# C_3.net
KiCad netlist of a schematic drawn in EasyEDA Pro
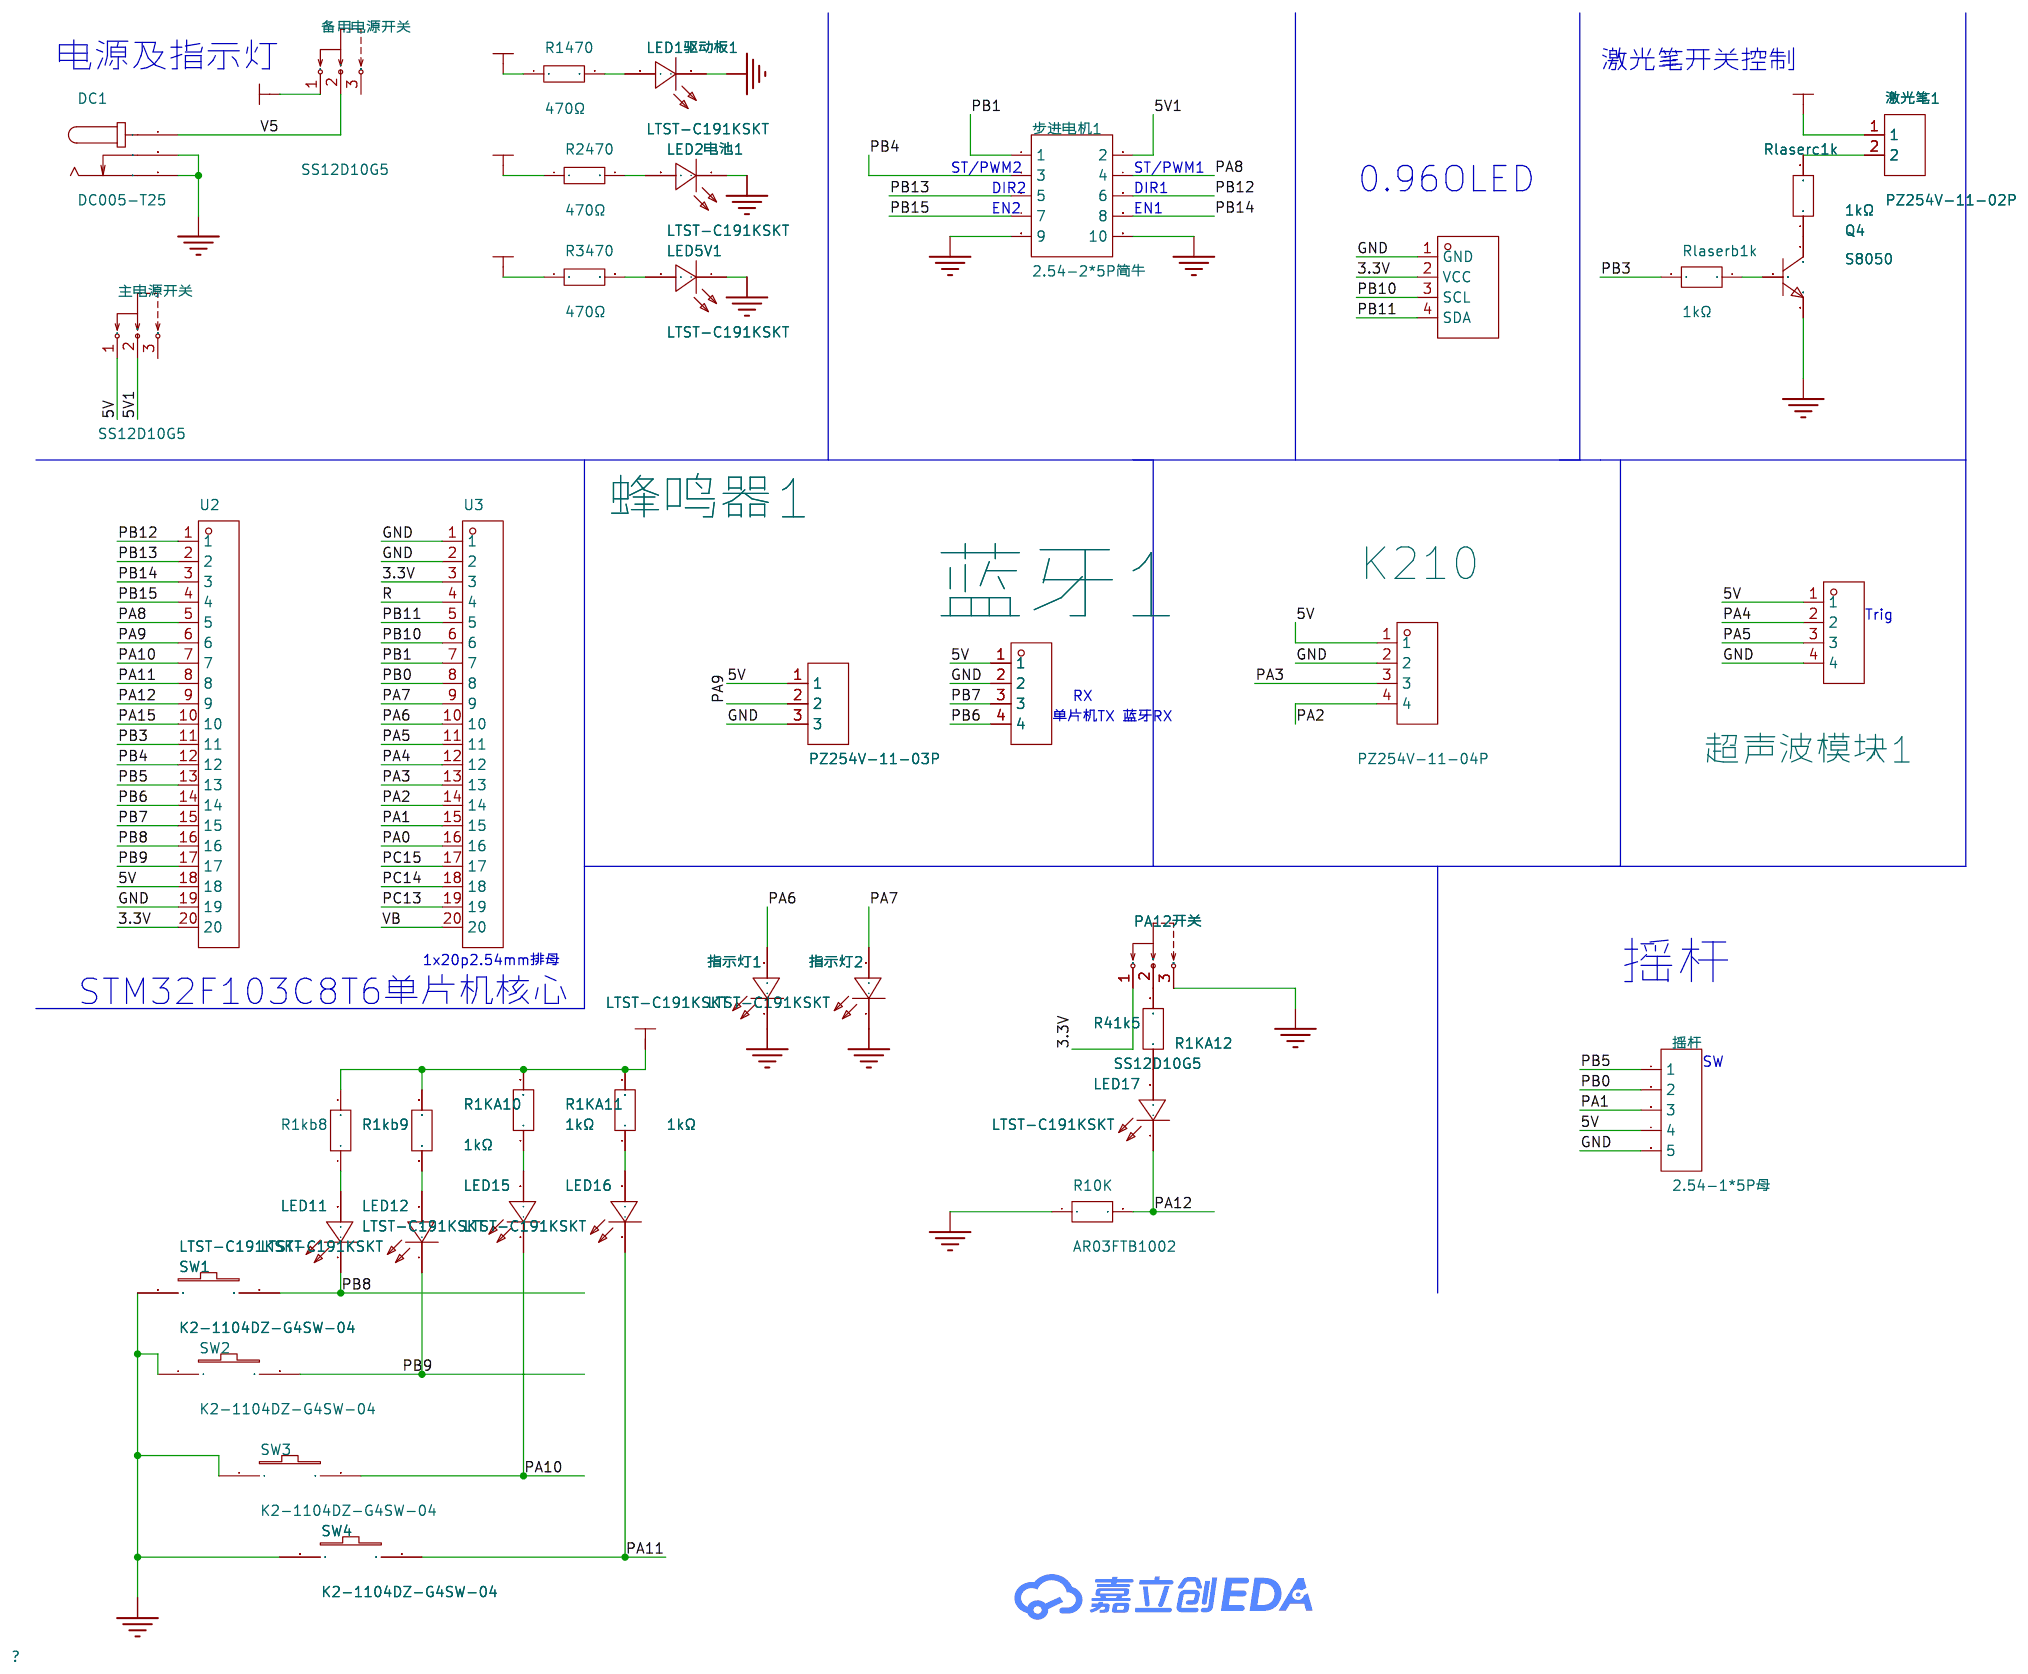
[diagram p0: schematic sheet]

(export (version "E")
  (design (tool "Eeschema 10.0.6"))
  (components
    (comp (ref "DC1")
      (value "DC005-T25")
      (footprint "easyedapro:DC-IN-TH_DC-005-20A-1")
      (description "触点内径:2.5mm;触点外径:6.3mm;额定电流:-;额定电压:-;")
      (fields (field (name "Manufacturer") "SOFNG(硕方)"))
      (libsource (lib "easyedapro") (part "DC005-2.5MM"))
    )
    (comp (ref "K210")
      (value "PZ254V-11-04P")
      (footprint "easyedapro:HDR-TH_4P-P2.54-V-M")
      (fields (field (name "Manufacturer") "XFCN(兴飞)"))
      (libsource (lib "easyedapro") (part "PZ254V-11-04P_C2691448"))
    )
    (comp (ref "LED1驱动板1")
      (value "LTST-C191KSKT")
      (footprint "easyedapro:LED0603-RD-YELLOW")
      (fields (field (name "Manufacturer") "LITEON(光宝)"))
      (libsource (lib "easyedapro") (part "LTST-C191KSKT"))
    )
    (comp (ref "LED2电池1")
      (value "LTST-C191KSKT")
      (footprint "easyedapro:LED0603-RD-YELLOW")
      (fields (field (name "Manufacturer") "LITEON(光宝)"))
      (libsource (lib "easyedapro") (part "LTST-C191KSKT"))
    )
    (comp (ref "LED5V1")
      (value "LTST-C191KSKT")
      (footprint "easyedapro:LED0603-RD-YELLOW")
      (fields (field (name "Manufacturer") "LITEON(光宝)"))
      (libsource (lib "easyedapro") (part "LTST-C191KSKT"))
    )
    (comp (ref "LED11")
      (value "LTST-C191KSKT")
      (footprint "easyedapro:LED0603-RD-YELLOW")
      (fields (field (name "Manufacturer") "LITEON(光宝)"))
      (libsource (lib "easyedapro") (part "LTST-C191KSKT"))
    )
    (comp (ref "LED12")
      (value "LTST-C191KSKT")
      (footprint "easyedapro:LED0603-RD-YELLOW")
      (fields (field (name "Manufacturer") "LITEON(光宝)"))
      (libsource (lib "easyedapro") (part "LTST-C191KSKT"))
    )
    (comp (ref "LED15")
      (value "LTST-C191KSKT")
      (footprint "easyedapro:LED0603-RD-YELLOW")
      (fields (field (name "Manufacturer") "LITEON(光宝)"))
      (libsource (lib "easyedapro") (part "LTST-C191KSKT"))
    )
    (comp (ref "LED16")
      (value "LTST-C191KSKT")
      (footprint "easyedapro:LED0603-RD-YELLOW")
      (fields (field (name "Manufacturer") "LITEON(光宝)"))
      (libsource (lib "easyedapro") (part "LTST-C191KSKT"))
    )
    (comp (ref "LED17")
      (value "LTST-C191KSKT")
      (footprint "easyedapro:LED0603-RD-YELLOW")
      (fields (field (name "Manufacturer") "LITEON(光宝)"))
      (libsource (lib "easyedapro") (part "LTST-C191KSKT"))
    )
    (comp (ref "OLED1")
      (value "HS96L03W2C03")
      (footprint "easyedapro:OLED-TH_L27.8-W27.2-P2.54_C9900033791")
      (description "主控芯片:SSD1315;接口类型:I2C;尺寸(inch):0.96;像素分辨率:128x64;")
      (fields (field (name "Manufacturer") "HS(汉昇)"))
      (libsource (lib "easyedapro") (part "HS96L03W2C03"))
    )
    (comp (ref "PA12开关")
      (value "SS12D10G5")
      (footprint "easyedapro:SW-TH_SHOU-HAN_SS12D10G4")
      (description "电路结构:单刀双掷;安装方式:直插;额定电流(DC):2A;额定电压(DC):125V;机械寿命:3千次;")
      (fields (field (name "Manufacturer") "SHOU HAN(首韩)"))
      (libsource (lib "easyedapro") (part "SS12D10G5"))
    )
    (comp (ref "Q4")
      (value "S8050")
      (footprint "easyedapro:SOT-23-3_L2.9-W1.6-P1.90-LS2.8-BR")
      (description "晶体管类型:NPN;集电极电流(Ic):500mA;集射极击穿电压(Vceo):25V;功率(Pd):300mW;")
      (fields (field (name "Manufacturer") "Hottech(合科泰)"))
      (libsource (lib "easyedapro") (part "S8050_C181158"))
    )
    (comp (ref "R1KA10")
      (value "1kΩ")
      (footprint "easyedapro:R0603")
      (description "电阻类型:厚膜电阻;阻值:1kΩ;精度:±1%;功率:100mW;最大工作电压:75V;")
      (fields (field (name "Manufacturer Part") "FCR0603F1K") (field (name "Manufacturer") "VO(翔胜)"))
      (libsource (lib "easyedapro") (part "FCR0603F1K"))
    )
    (comp (ref "R1KA11")
      (value "1kΩ")
      (footprint "easyedapro:R0603")
      (description "电阻类型:厚膜电阻;阻值:1kΩ;精度:±1%;功率:100mW;最大工作电压:75V;")
      (fields (field (name "Manufacturer Part") "FCR0603F1K") (field (name "Manufacturer") "VO(翔胜)"))
      (libsource (lib "easyedapro") (part "FCR0603F1K"))
    )
    (comp (ref "R1kb8")
      (value "1kΩ")
      (footprint "easyedapro:R0603")
      (description "电阻类型:厚膜电阻;阻值:1kΩ;精度:±1%;功率:100mW;最大工作电压:75V;")
      (fields (field (name "Manufacturer Part") "FCR0603F1K") (field (name "Manufacturer") "VO(翔胜)"))
      (libsource (lib "easyedapro") (part "FCR0603F1K"))
    )
    (comp (ref "R1kb9")
      (value "1kΩ")
      (footprint "easyedapro:R0603")
      (description "电阻类型:厚膜电阻;阻值:1kΩ;精度:±1%;功率:100mW;最大工作电压:75V;")
      (fields (field (name "Manufacturer Part") "FCR0603F1K") (field (name "Manufacturer") "VO(翔胜)"))
      (libsource (lib "easyedapro") (part "FCR0603F1K"))
    )
    (comp (ref "R10K")
      (value "AR03FTB1002")
      (footprint "easyedapro:R0603")
      (fields (field (name "Manufacturer") "Viking(光颉)"))
      (libsource (lib "easyedapro") (part "AR03FTB1002"))
    )
    (comp (ref "R41k5")
      (value "1kΩ")
      (footprint "easyedapro:R0603")
      (description "电阻类型:厚膜电阻;阻值:1kΩ;精度:±1%;功率:100mW;最大工作电压:75V;")
      (fields (field (name "Manufacturer Part") "FCR0603F1K") (field (name "Manufacturer") "VO(翔胜)"))
      (libsource (lib "easyedapro") (part "FCR0603F1K"))
    )
    (comp (ref "R1470")
      (value "470Ω")
      (footprint "easyedapro:R0603")
      (description "电阻类型:厚膜电阻;阻值:470Ω;精度:±1%;功率:100mW;最大工作电压:75V;温度系数:±100ppm/°C;")
      (fields
        (field (name "Manufacturer Part") "0603WAF4700T5E")
        (field (name "Manufacturer") "UNI-ROYAL(厚声)")
      )
      (libsource (lib "easyedapro") (part "0603WAF4700T5E"))
    )
    (comp (ref "R2470")
      (value "470Ω")
      (footprint "easyedapro:R0603")
      (description "电阻类型:厚膜电阻;阻值:470Ω;精度:±1%;功率:100mW;最大工作电压:75V;温度系数:±100ppm/°C;")
      (fields
        (field (name "Manufacturer Part") "0603WAF4700T5E")
        (field (name "Manufacturer") "UNI-ROYAL(厚声)")
      )
      (libsource (lib "easyedapro") (part "0603WAF4700T5E"))
    )
    (comp (ref "R3470")
      (value "470Ω")
      (footprint "easyedapro:R0603")
      (description "电阻类型:厚膜电阻;阻值:470Ω;精度:±1%;功率:100mW;最大工作电压:75V;温度系数:±100ppm/°C;")
      (fields
        (field (name "Manufacturer Part") "0603WAF4700T5E")
        (field (name "Manufacturer") "UNI-ROYAL(厚声)")
      )
      (libsource (lib "easyedapro") (part "0603WAF4700T5E"))
    )
    (comp (ref "Rlaserb1k")
      (value "1kΩ")
      (footprint "easyedapro:R0603")
      (description "电阻类型:厚膜电阻;阻值:1kΩ;精度:±1%;功率:100mW;最大工作电压:75V;")
      (fields (field (name "Manufacturer Part") "FCR0603F1K") (field (name "Manufacturer") "VO(翔胜)"))
      (libsource (lib "easyedapro") (part "FCR0603F1K"))
    )
    (comp (ref "Rlaserc1k")
      (value "1kΩ")
      (footprint "easyedapro:R0603")
      (description "电阻类型:厚膜电阻;阻值:1kΩ;精度:±1%;功率:100mW;最大工作电压:75V;")
      (fields (field (name "Manufacturer Part") "FCR0603F1K") (field (name "Manufacturer") "VO(翔胜)"))
      (libsource (lib "easyedapro") (part "FCR0603F1K"))
    )
    (comp (ref "SW1")
      (value "K2-1104DZ-G4SW-04")
      (footprint "easyedapro:KEY-TH_2P-L6.0-W6.0-P5.00")
      (description "作用力:250gf;安装方式:直插;开关长度:6mm;开关宽度:6mm;开关高度:7mm;触点电流:50mA;额定电压(DC):12V;绝缘电阻:100MΩ;机械寿命:10万次;")
      (fields (field (name "Manufacturer") "韩国韩荣"))
      (libsource (lib "easyedapro") (part "K2-1104DZ-G4SW-04"))
    )
    (comp (ref "SW2")
      (value "K2-1104DZ-G4SW-04")
      (footprint "easyedapro:KEY-TH_2P-L6.0-W6.0-P5.00")
      (description "作用力:250gf;安装方式:直插;开关长度:6mm;开关宽度:6mm;开关高度:7mm;触点电流:50mA;额定电压(DC):12V;绝缘电阻:100MΩ;机械寿命:10万次;")
      (fields (field (name "Manufacturer") "韩国韩荣"))
      (libsource (lib "easyedapro") (part "K2-1104DZ-G4SW-04"))
    )
    (comp (ref "SW3")
      (value "K2-1104DZ-G4SW-04")
      (footprint "easyedapro:KEY-TH_2P-L6.0-W6.0-P5.00")
      (description "作用力:250gf;安装方式:直插;开关长度:6mm;开关宽度:6mm;开关高度:7mm;触点电流:50mA;额定电压(DC):12V;绝缘电阻:100MΩ;机械寿命:10万次;")
      (fields (field (name "Manufacturer") "韩国韩荣"))
      (libsource (lib "easyedapro") (part "K2-1104DZ-G4SW-04"))
    )
    (comp (ref "SW4")
      (value "K2-1104DZ-G4SW-04")
      (footprint "easyedapro:KEY-TH_2P-L6.0-W6.0-P5.00")
      (description "作用力:250gf;安装方式:直插;开关长度:6mm;开关宽度:6mm;开关高度:7mm;触点电流:50mA;额定电压(DC):12V;绝缘电阻:100MΩ;机械寿命:10万次;")
      (fields (field (name "Manufacturer") "韩国韩荣"))
      (libsource (lib "easyedapro") (part "K2-1104DZ-G4SW-04"))
    )
    (comp (ref "U2")
      (value "KH-2FH-1X20P-H4.3")
      (footprint "easyedapro:HDR-TH_20P-P2.00-V-F-A")
      (fields (field (name "Manufacturer") "kinghelm(金航标)"))
      (libsource (lib "easyedapro") (part "KH-2FH-1X20P-H4.3"))
    )
    (comp (ref "U3")
      (value "KH-2FH-1X20P-H4.3")
      (footprint "easyedapro:HDR-TH_20P-P2.00-V-F-A")
      (fields (field (name "Manufacturer") "kinghelm(金航标)"))
      (libsource (lib "easyedapro") (part "KH-2FH-1X20P-H4.3"))
    )
    (comp (ref "主电源开关")
      (value "SS12D10G5")
      (footprint "easyedapro:SW-TH_SHOU-HAN_SS12D10G4")
      (description "电路结构:单刀双掷;安装方式:直插;额定电流(DC):2A;额定电压(DC):125V;机械寿命:3千次;")
      (fields (field (name "Manufacturer") "SHOU HAN(首韩)"))
      (libsource (lib "easyedapro") (part "SS12D10G5"))
    )
    (comp (ref "备用电源开关")
      (value "SS12D10G5")
      (footprint "easyedapro:SW-TH_SHOU-HAN_SS12D10G4")
      (description "电路结构:单刀双掷;安装方式:直插;额定电流(DC):2A;额定电压(DC):125V;机械寿命:3千次;")
      (fields (field (name "Manufacturer") "SHOU HAN(首韩)"))
      (libsource (lib "easyedapro") (part "SS12D10G5"))
    )
    (comp (ref "指示灯1")
      (value "LTST-C191KSKT")
      (footprint "easyedapro:LED0603-RD-YELLOW")
      (fields (field (name "Manufacturer") "LITEON(光宝)"))
      (libsource (lib "easyedapro") (part "LTST-C191KSKT"))
    )
    (comp (ref "指示灯2")
      (value "LTST-C191KSKT")
      (footprint "easyedapro:LED0603-RD-YELLOW")
      (fields (field (name "Manufacturer") "LITEON(光宝)"))
      (libsource (lib "easyedapro") (part "LTST-C191KSKT"))
    )
    (comp (ref "摇杆")
      (value "2.54-1*5P母")
      (footprint "easyedapro:HDR-TH_5P-P2.54-V-F")
      (description "插孔结构:1x5P;间距:2.54mm;行距:-;安装类型:直插;排数:单排;总孔位数:5P;塑高:-;触头材质:-;触头镀层:-;")
      (fields (field (name "Manufacturer") "BOOMELE(博穆精密)"))
      (libsource (lib "easyedapro") (part "Header-Female-2.54_1x5"))
    )
    (comp (ref "步进电机1")
      (value "2.54-2*5P简牛")
      (footprint "easyedapro:IDC-TH_10P-P2.54_C5665")
      (description "连接器类型:简牛座;间距:2.54mm;结构:2x5P;封装形式:直插;行距:2.54mm;排数:2;每排PIN数:5;触头材质:-;触头镀层:-;")
      (fields (field (name "Manufacturer") "BOOMELE(博穆精密)"))
      (libsource (lib "easyedapro") (part "HDR-IDC-2.54-2X5P"))
    )
    (comp (ref "激光笔1")
      (value "PZ254V-11-02P")
      (footprint "easyedapro:HDR-TH_2P-P2.54-V-M")
      (fields (field (name "Manufacturer") "XFCN(兴飞)"))
      (libsource (lib "easyedapro") (part "PZ254V-11-02P"))
    )
    (comp (ref "蓝牙1")
      (value "2.54-1*4P母")
      (footprint "easyedapro:HDR-TH_4P-P2.54-V-F")
      (fields (field (name "Manufacturer") "BOOMELE(博穆精密)"))
      (libsource (lib "easyedapro") (part "2.54-1*4P母"))
    )
    (comp (ref "蜂鸣器1")
      (value "PZ254V-11-03P")
      (footprint "easyedapro:HDR-TH_3P-P2.54-V-M")
      (fields (field (name "Manufacturer") "XFCN(兴飞)"))
      (libsource (lib "easyedapro") (part "PZ254V-11-03P_C2937625"))
    )
    (comp (ref "超声波模块1")
      (value "KH-2.54FH-1X4P-H8.5")
      (footprint "easyedapro:HDR-TH_4P-P2.54-V-F")
      (fields (field (name "Manufacturer") "kinghelm(金航标)"))
      (libsource (lib "easyedapro") (part "KH-2.54FH-1X4P-H8.5"))
    )
  )
  (nets
    (net (code "1") (name "/PA0") (class "Default")
      (node (ref "U3") (pin "16") (pinfunction "16_16") (pintype "unspecified"))
    )
    (net (code "2") (name "/PA1") (class "Default")
      (node (ref "U3") (pin "15") (pinfunction "15_15") (pintype "unspecified"))
      (node (ref "摇杆") (pin "3") (pinfunction "3_3") (pintype "input"))
    )
    (net (code "3") (name "/PA2") (class "Default")
      (node (ref "K210") (pin "4") (pinfunction "4_4") (pintype "unspecified"))
      (node (ref "U3") (pin "14") (pinfunction "14_14") (pintype "unspecified"))
    )
    (net (code "4") (name "/PA3") (class "Default")
      (node (ref "K210") (pin "3") (pinfunction "3_3") (pintype "unspecified"))
      (node (ref "U3") (pin "13") (pinfunction "13_13") (pintype "unspecified"))
    )
    (net (code "5") (name "/PA4") (class "Default")
      (node (ref "U3") (pin "12") (pinfunction "12_12") (pintype "unspecified"))
      (node (ref "超声波模块1") (pin "2") (pinfunction "2_2") (pintype "unspecified"))
    )
    (net (code "6") (name "/PA5") (class "Default")
      (node (ref "U3") (pin "11") (pinfunction "11_11") (pintype "unspecified"))
      (node (ref "超声波模块1") (pin "3") (pinfunction "3_3") (pintype "unspecified"))
    )
    (net (code "7") (name "/PA6") (class "Default")
      (node (ref "U3") (pin "10") (pinfunction "10_10") (pintype "unspecified"))
      (node (ref "指示灯1") (pin "2") (pinfunction "+_2") (pintype "unspecified"))
    )
    (net (code "8") (name "/PA7") (class "Default")
      (node (ref "U3") (pin "9") (pinfunction "9_9") (pintype "unspecified"))
      (node (ref "指示灯2") (pin "2") (pinfunction "+_2") (pintype "unspecified"))
    )
    (net (code "9") (name "/PA8") (class "Default")
      (node (ref "U2") (pin "5") (pinfunction "5_5") (pintype "unspecified"))
      (node (ref "步进电机1") (pin "4") (pinfunction "4_4") (pintype "unspecified"))
    )
    (net (code "10") (name "/PA9") (class "Default")
      (node (ref "U2") (pin "6") (pinfunction "6_6") (pintype "unspecified"))
      (node (ref "蜂鸣器1") (pin "2") (pinfunction "2_2") (pintype "unspecified"))
    )
    (net (code "11") (name "/PA10") (class "Default")
      (node (ref "LED15") (pin "1") (pinfunction "-_1") (pintype "unspecified"))
      (node (ref "SW3") (pin "2") (pinfunction "2_2") (pintype "input"))
      (node (ref "U2") (pin "7") (pinfunction "7_7") (pintype "unspecified"))
    )
    (net (code "12") (name "/PA11") (class "Default")
      (node (ref "LED16") (pin "1") (pinfunction "-_1") (pintype "unspecified"))
      (node (ref "SW4") (pin "2") (pinfunction "2_2") (pintype "input"))
      (node (ref "U2") (pin "8") (pinfunction "8_8") (pintype "unspecified"))
    )
    (net (code "13") (name "/PA12") (class "Default")
      (node (ref "LED17") (pin "1") (pinfunction "-_1") (pintype "unspecified"))
      (node (ref "R10K") (pin "2") (pinfunction "2_2") (pintype "unspecified"))
      (node (ref "U2") (pin "9") (pinfunction "9_9") (pintype "unspecified"))
    )
    (net (code "14") (name "/PA15") (class "Default")
      (node (ref "U2") (pin "10") (pinfunction "10_10") (pintype "unspecified"))
    )
    (net (code "15") (name "/PB0") (class "Default")
      (node (ref "U3") (pin "8") (pinfunction "8_8") (pintype "unspecified"))
      (node (ref "摇杆") (pin "2") (pinfunction "2_2") (pintype "input"))
    )
    (net (code "16") (name "/PB1") (class "Default")
      (node (ref "U3") (pin "7") (pinfunction "7_7") (pintype "unspecified"))
      (node (ref "步进电机1") (pin "1") (pinfunction "1_1") (pintype "unspecified"))
    )
    (net (code "17") (name "/PB3") (class "Default")
      (node (ref "Rlaserb1k") (pin "2") (pinfunction "2_2") (pintype "unspecified"))
      (node (ref "U2") (pin "11") (pinfunction "11_11") (pintype "unspecified"))
    )
    (net (code "18") (name "/PB4") (class "Default")
      (node (ref "U2") (pin "12") (pinfunction "12_12") (pintype "unspecified"))
      (node (ref "步进电机1") (pin "3") (pinfunction "3_3") (pintype "unspecified"))
    )
    (net (code "19") (name "/PB5") (class "Default")
      (node (ref "U2") (pin "13") (pinfunction "13_13") (pintype "unspecified"))
      (node (ref "摇杆") (pin "1") (pinfunction "1_1") (pintype "input"))
    )
    (net (code "20") (name "/PB6") (class "Default")
      (node (ref "U2") (pin "14") (pinfunction "14_14") (pintype "unspecified"))
      (node (ref "蓝牙1") (pin "4") (pinfunction "4_4") (pintype "unspecified"))
    )
    (net (code "21") (name "/PB7") (class "Default")
      (node (ref "U2") (pin "15") (pinfunction "15_15") (pintype "unspecified"))
      (node (ref "蓝牙1") (pin "3") (pinfunction "3_3") (pintype "unspecified"))
    )
    (net (code "22") (name "/PB8") (class "Default")
      (node (ref "LED11") (pin "1") (pinfunction "-_1") (pintype "unspecified"))
      (node (ref "SW1") (pin "2") (pinfunction "2_2") (pintype "input"))
      (node (ref "U2") (pin "16") (pinfunction "16_16") (pintype "unspecified"))
    )
    (net (code "23") (name "/PB9") (class "Default")
      (node (ref "LED12") (pin "1") (pinfunction "-_1") (pintype "unspecified"))
      (node (ref "SW2") (pin "2") (pinfunction "2_2") (pintype "input"))
      (node (ref "U2") (pin "17") (pinfunction "17_17") (pintype "unspecified"))
    )
    (net (code "24") (name "/PB10") (class "Default")
      (node (ref "OLED1") (pin "3") (pinfunction "SCL_3") (pintype "unspecified"))
      (node (ref "U3") (pin "6") (pinfunction "6_6") (pintype "unspecified"))
    )
    (net (code "25") (name "/PB11") (class "Default")
      (node (ref "OLED1") (pin "4") (pinfunction "SDA_4") (pintype "unspecified"))
      (node (ref "U3") (pin "5") (pinfunction "5_5") (pintype "unspecified"))
    )
    (net (code "26") (name "/PB12") (class "Default")
      (node (ref "U2") (pin "1") (pinfunction "1_1") (pintype "unspecified"))
      (node (ref "步进电机1") (pin "6") (pinfunction "6_6") (pintype "unspecified"))
    )
    (net (code "27") (name "/PB13") (class "Default")
      (node (ref "U2") (pin "2") (pinfunction "2_2") (pintype "unspecified"))
      (node (ref "步进电机1") (pin "5") (pinfunction "5_5") (pintype "unspecified"))
    )
    (net (code "28") (name "/PB14") (class "Default")
      (node (ref "U2") (pin "3") (pinfunction "3_3") (pintype "unspecified"))
      (node (ref "步进电机1") (pin "8") (pinfunction "8_8") (pintype "unspecified"))
    )
    (net (code "29") (name "/PB15") (class "Default")
      (node (ref "U2") (pin "4") (pinfunction "4_4") (pintype "unspecified"))
      (node (ref "步进电机1") (pin "7") (pinfunction "7_7") (pintype "unspecified"))
    )
    (net (code "30") (name "/PC13") (class "Default")
      (node (ref "U3") (pin "19") (pinfunction "19_19") (pintype "unspecified"))
    )
    (net (code "31") (name "/PC14") (class "Default")
      (node (ref "U3") (pin "18") (pinfunction "18_18") (pintype "unspecified"))
    )
    (net (code "32") (name "/PC15") (class "Default")
      (node (ref "U3") (pin "17") (pinfunction "17_17") (pintype "unspecified"))
    )
    (net (code "33") (name "/R") (class "Default")
      (node (ref "U3") (pin "4") (pinfunction "4_4") (pintype "unspecified"))
    )
    (net (code "34") (name "/VB") (class "Default")
      (node (ref "U3") (pin "20") (pinfunction "20_20") (pintype "unspecified"))
    )
    (net (code "35") (name "3.3V") (class "Default")
      (node (ref "OLED1") (pin "2") (pinfunction "VCC_2") (pintype "unspecified"))
      (node (ref "PA12开关") (pin "1") (pinfunction "1_1") (pintype "unspecified"))
      (node (ref "R1KA10") (pin "2") (pinfunction "2_2") (pintype "unspecified"))
      (node (ref "R1KA11") (pin "2") (pinfunction "2_2") (pintype "unspecified"))
      (node (ref "R1kb8") (pin "2") (pinfunction "2_2") (pintype "unspecified"))
      (node (ref "R1kb9") (pin "2") (pinfunction "2_2") (pintype "unspecified"))
      (node (ref "U2") (pin "20") (pinfunction "20_20") (pintype "unspecified"))
      (node (ref "U3") (pin "3") (pinfunction "3_3") (pintype "unspecified"))
    )
    (net (code "36") (name "5V") (class "Default")
      (node (ref "K210") (pin "1") (pinfunction "1_1") (pintype "unspecified"))
      (node (ref "R3470") (pin "1") (pinfunction "1_1") (pintype "input"))
      (node (ref "U2") (pin "18") (pinfunction "18_18") (pintype "unspecified"))
      (node (ref "主电源开关") (pin "1") (pinfunction "1_1") (pintype "unspecified"))
      (node (ref "备用电源开关") (pin "1") (pinfunction "1_1") (pintype "unspecified"))
      (node (ref "摇杆") (pin "4") (pinfunction "4_4") (pintype "input"))
      (node (ref "激光笔1") (pin "1") (pinfunction "1_1") (pintype "unspecified"))
      (node (ref "蓝牙1") (pin "1") (pinfunction "1_1") (pintype "unspecified"))
      (node (ref "蜂鸣器1") (pin "1") (pinfunction "1_1") (pintype "unspecified"))
      (node (ref "超声波模块1") (pin "1") (pinfunction "1_1") (pintype "unspecified"))
    )
    (net (code "37") (name "5V1") (class "Default")
      (node (ref "R1470") (pin "1") (pinfunction "1_1") (pintype "input"))
      (node (ref "主电源开关") (pin "2") (pinfunction "2_2") (pintype "unspecified"))
      (node (ref "步进电机1") (pin "2") (pinfunction "2_2") (pintype "unspecified"))
    )
    (net (code "38") (name "GND") (class "Default")
      (node (ref "DC1") (pin "2") (pinfunction "2_2") (pintype "unspecified"))
      (node (ref "DC1") (pin "3") (pinfunction "3_3") (pintype "unspecified"))
      (node (ref "K210") (pin "2") (pinfunction "2_2") (pintype "unspecified"))
      (node (ref "LED1驱动板1") (pin "1") (pinfunction "-_1") (pintype "unspecified"))
      (node (ref "LED2电池1") (pin "1") (pinfunction "-_1") (pintype "unspecified"))
      (node (ref "LED5V1") (pin "1") (pinfunction "-_1") (pintype "unspecified"))
      (node (ref "OLED1") (pin "1") (pinfunction "GND_1") (pintype "unspecified"))
      (node (ref "PA12开关") (pin "3") (pinfunction "3_3") (pintype "unspecified"))
      (node (ref "Q4") (pin "2") (pinfunction "2_2") (pintype "input"))
      (node (ref "R10K") (pin "1") (pinfunction "1_1") (pintype "unspecified"))
      (node (ref "SW1") (pin "1") (pinfunction "1_1") (pintype "input"))
      (node (ref "SW2") (pin "1") (pinfunction "1_1") (pintype "input"))
      (node (ref "SW3") (pin "1") (pinfunction "1_1") (pintype "input"))
      (node (ref "SW4") (pin "1") (pinfunction "1_1") (pintype "input"))
      (node (ref "U2") (pin "19") (pinfunction "19_19") (pintype "unspecified"))
      (node (ref "U3") (pin "1") (pinfunction "1_1") (pintype "unspecified"))
      (node (ref "U3") (pin "2") (pinfunction "2_2") (pintype "unspecified"))
      (node (ref "指示灯1") (pin "1") (pinfunction "-_1") (pintype "unspecified"))
      (node (ref "指示灯2") (pin "1") (pinfunction "-_1") (pintype "unspecified"))
      (node (ref "摇杆") (pin "5") (pinfunction "5_5") (pintype "input"))
      (node (ref "步进电机1") (pin "10") (pinfunction "10_10") (pintype "unspecified"))
      (node (ref "步进电机1") (pin "9") (pinfunction "9_9") (pintype "unspecified"))
      (node (ref "蓝牙1") (pin "2") (pinfunction "2_2") (pintype "unspecified"))
      (node (ref "蜂鸣器1") (pin "3") (pinfunction "3_3") (pintype "unspecified"))
      (node (ref "超声波模块1") (pin "4") (pinfunction "4_4") (pintype "unspecified"))
    )
    (net (code "39") (name "Net-(LED1驱动板1-+)") (class "Default")
      (node (ref "LED1驱动板1") (pin "2") (pinfunction "+_2") (pintype "unspecified"))
      (node (ref "R1470") (pin "2") (pinfunction "2_2") (pintype "input"))
    )
    (net (code "40") (name "Net-(LED2电池1-+)") (class "Default")
      (node (ref "LED2电池1") (pin "2") (pinfunction "+_2") (pintype "unspecified"))
      (node (ref "R2470") (pin "2") (pinfunction "2_2") (pintype "input"))
    )
    (net (code "41") (name "Net-(LED5V1-+)") (class "Default")
      (node (ref "LED5V1") (pin "2") (pinfunction "+_2") (pintype "unspecified"))
      (node (ref "R3470") (pin "2") (pinfunction "2_2") (pintype "input"))
    )
    (net (code "42") (name "Net-(LED11-+)") (class "Default")
      (node (ref "LED11") (pin "2") (pinfunction "+_2") (pintype "unspecified"))
      (node (ref "R1kb8") (pin "1") (pinfunction "1_1") (pintype "unspecified"))
    )
    (net (code "43") (name "Net-(LED12-+)") (class "Default")
      (node (ref "LED12") (pin "2") (pinfunction "+_2") (pintype "unspecified"))
      (node (ref "R1kb9") (pin "1") (pinfunction "1_1") (pintype "unspecified"))
    )
    (net (code "44") (name "Net-(LED15-+)") (class "Default")
      (node (ref "LED15") (pin "2") (pinfunction "+_2") (pintype "unspecified"))
      (node (ref "R1KA10") (pin "1") (pinfunction "1_1") (pintype "unspecified"))
    )
    (net (code "45") (name "Net-(LED16-+)") (class "Default")
      (node (ref "LED16") (pin "2") (pinfunction "+_2") (pintype "unspecified"))
      (node (ref "R1KA11") (pin "1") (pinfunction "1_1") (pintype "unspecified"))
    )
    (net (code "46") (name "Net-(LED17-+)") (class "Default")
      (node (ref "LED17") (pin "2") (pinfunction "+_2") (pintype "unspecified"))
      (node (ref "R41k5") (pin "1") (pinfunction "1_1") (pintype "unspecified"))
    )
    (net (code "47") (name "Net-(PA12开关-Pad2)") (class "Default")
      (node (ref "PA12开关") (pin "2") (pinfunction "2_2") (pintype "unspecified"))
      (node (ref "R41k5") (pin "2") (pinfunction "2_2") (pintype "unspecified"))
    )
    (net (code "48") (name "Net-(Q4-Pad1)") (class "Default")
      (node (ref "Q4") (pin "1") (pinfunction "1_1") (pintype "input"))
      (node (ref "Rlaserb1k") (pin "1") (pinfunction "1_1") (pintype "unspecified"))
    )
    (net (code "49") (name "Net-(Q4-Pad3)") (class "Default")
      (node (ref "Q4") (pin "3") (pinfunction "3_3") (pintype "input"))
      (node (ref "Rlaserc1k") (pin "1") (pinfunction "1_1") (pintype "unspecified"))
    )
    (net (code "50") (name "Net-(Rlaserc1k-Pad2)") (class "Default")
      (node (ref "Rlaserc1k") (pin "2") (pinfunction "2_2") (pintype "unspecified"))
      (node (ref "激光笔1") (pin "2") (pinfunction "2_2") (pintype "unspecified"))
    )
    (net (code "51") (name "V5") (class "Default")
      (node (ref "DC1") (pin "1") (pinfunction "1_1") (pintype "unspecified"))
      (node (ref "R2470") (pin "1") (pinfunction "1_1") (pintype "input"))
      (node (ref "备用电源开关") (pin "2") (pinfunction "2_2") (pintype "unspecified"))
    )
    (net (code "52") (name "unconnected-(主电源开关-Pad3)") (class "Default")
      (node (ref "主电源开关") (pin "3") (pinfunction "3_3") (pintype "unspecified"))
    )
    (net (code "53") (name "unconnected-(备用电源开关-Pad3)") (class "Default")
      (node (ref "备用电源开关") (pin "3") (pinfunction "3_3") (pintype "unspecified"))
    )
  )
)
